# MicrobitBoardSensor.net
KiCad netlist of a schematic drawn in Altium Designer
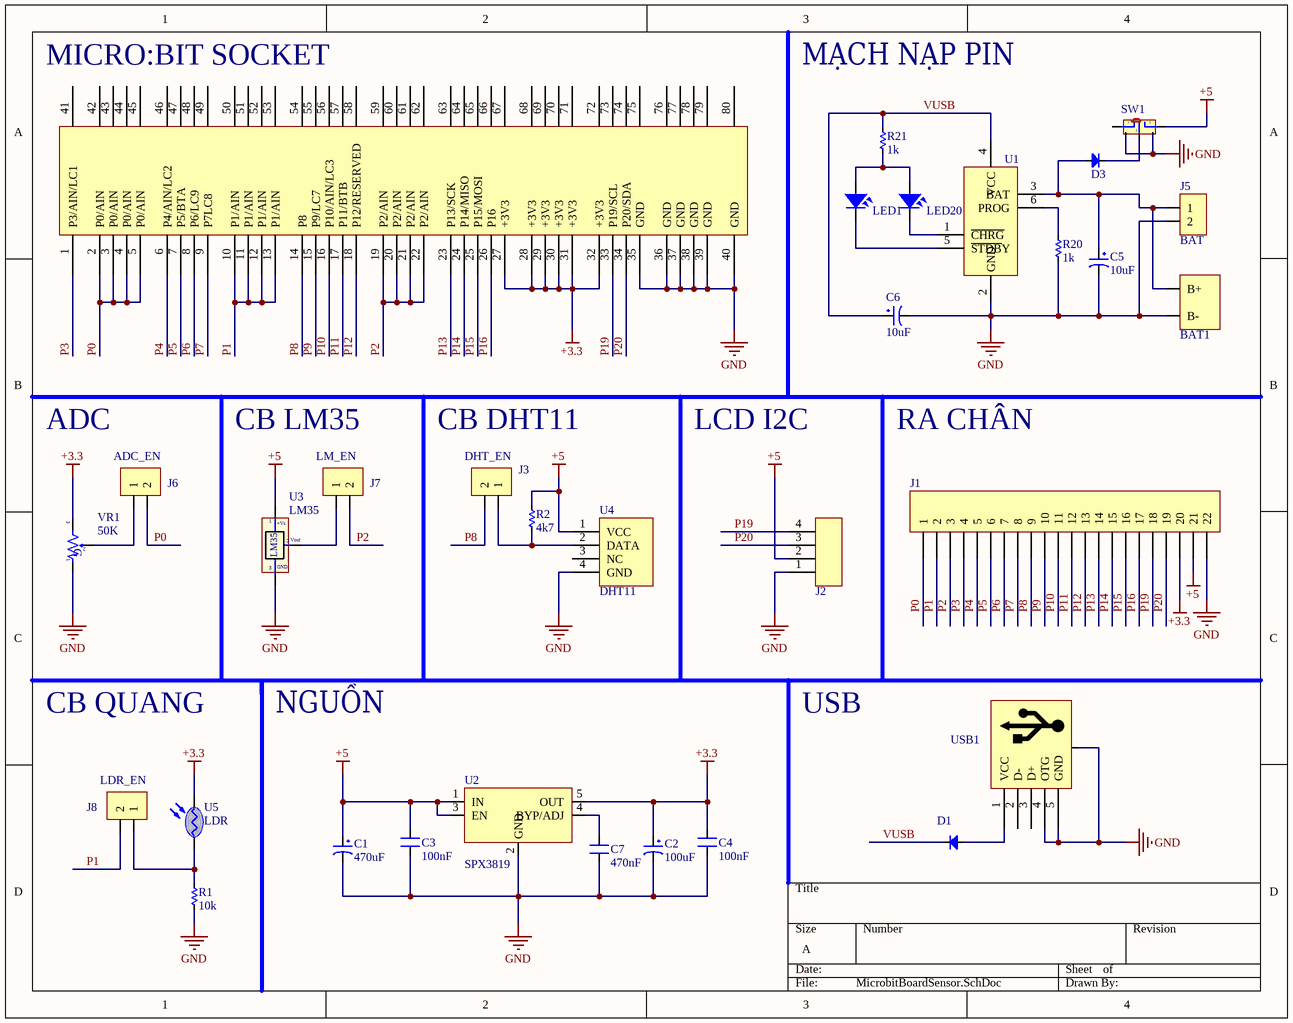
[diagram p0: MicrobitBoardSensor.SchDoc]

(export (version "E")
  (design (tool "Eeschema 10.0.6"))
  (components
    (comp (ref "BAT1")
      (value "BATERRY SOCKET")
      (footprint "BAT_SOCKET")
      (libsource (lib "User") (part "BAT_SOCKET"))
    )
    (comp (ref "BBC1")
      (value "BBC_SOCKET")
      (footprint "BBC_SK_DIP")
      (libsource (lib "microbit") (part "BBC_SOCKET"))
    )
    (comp (ref "C1")
      (value "470uF")
      (footprint "tu tantalum smd7343")
      (description "Dán")
      (libsource (lib "THU VIEN SCH_04042017_1") (part "Tu tantalum 470uF 10V SMD7343"))
    )
    (comp (ref "C2")
      (value "100uF")
      (footprint "tu tantalum smd3528")
      (description "Dán")
      (libsource (lib "THU VIEN SCH_04042017_1") (part "Tu tantalum 100uF 6.3V SMD3528"))
    )
    (comp (ref "C3") (value "100nF") (footprint "CN-SMD-0805") (libsource (lib "LIBRARY") (part "CN")))
    (comp (ref "C4") (value "100nF") (footprint "CN-SMD-0805") (libsource (lib "LIBRARY") (part "CN")))
    (comp (ref "C5")
      (value "10uF")
      (footprint "tu tantalum smd3528")
      (description "Dán")
      (libsource (lib "THU VIEN SCH_04042017_1") (part "Tu tantalum 10uF 16V SMD3528"))
    )
    (comp (ref "C6")
      (value "10uF")
      (footprint "tu tantalum smd3528")
      (description "Dán")
      (libsource (lib "") (part "Tu tantalum 10uF 16V SMD3528_1"))
    )
    (comp (ref "C7") (value "470nF") (footprint "CN-SMD-0805") (libsource (lib "LIBRARY") (part "CN")))
    (comp (ref "D1")
      (value "SS34")
      (footprint "DIO-SMD-123")
      (description "Default Diode")
      (fields (field (name "PUBLISHER") "Altium Limited"))
      (libsource (lib "LIBRARY") (part "Diode SMD"))
    )
    (comp (ref "D3")
      (value "SS34")
      (footprint "DIO-SMD-123")
      (description "Default Diode")
      (fields (field (name "PUBLISHER") "Altium Limited"))
      (libsource (lib "LIBRARY") (part "Diode SMD"))
    )
    (comp (ref "J1")
      (value "JP22")
      (footprint "JP22-D1T")
      (description "WR-PHD 2.54 mm Angled Socket Header")
      (fields
        (field (name "MANUFACTURER") "Würth Elektronik eiSos GmbH")
        (field (name "PARTNO") "613022143121")
        (field (name "CREATED BY") "Karrer Zheng")
      )
      (libsource (lib "LIBRARY") (part "JP22"))
    )
    (comp (ref "J2") (value "LCD IIC") (footprint "XH2.54-4P") (libsource (lib "User") (part "XH2.54-4P")))
    (comp (ref "J3")
      (value "DHT_EN")
      (footprint "JP2-CLOSED")
      (description "WR-PHD 2.54 mm Angled Socket Header")
      (fields
        (field (name "MANUFACTURER") "Würth Elektronik eiSos GmbH")
        (field (name "PARTNO") "613002143121")
        (field (name "CREATED BY") "Karrer Zheng")
      )
      (libsource (lib "") (part "JP2_1"))
    )
    (comp (ref "J5")
      (value "BAT")
      (footprint "JP2-D1T")
      (description "WR-PHD 2.54 mm Angled Socket Header")
      (fields
        (field (name "MANUFACTURER") "Würth Elektronik eiSos GmbH")
        (field (name "PARTNO") "613002143121")
        (field (name "CREATED BY") "Karrer Zheng")
      )
      (libsource (lib "") (part "JP2_1"))
    )
    (comp (ref "J6")
      (value "ADC_EN")
      (footprint "JP2-CLOSED")
      (description "WR-PHD 2.54 mm Angled Socket Header")
      (fields
        (field (name "MANUFACTURER") "Würth Elektronik eiSos GmbH")
        (field (name "PARTNO") "613002143121")
        (field (name "CREATED BY") "Karrer Zheng")
      )
      (libsource (lib "LIBRARY") (part "JP2"))
    )
    (comp (ref "J7")
      (value "LM_EN")
      (footprint "JP2-CLOSED")
      (description "WR-PHD 2.54 mm Angled Socket Header")
      (fields
        (field (name "MANUFACTURER") "Würth Elektronik eiSos GmbH")
        (field (name "PARTNO") "613002143121")
        (field (name "CREATED BY") "Karrer Zheng")
      )
      (libsource (lib "LIBRARY") (part "JP2"))
    )
    (comp (ref "J8")
      (value "LDR_EN")
      (footprint "JP2-CLOSED")
      (description "WR-PHD 2.54 mm Angled Socket Header")
      (fields
        (field (name "MANUFACTURER") "Würth Elektronik eiSos GmbH")
        (field (name "PARTNO") "613002143121")
        (field (name "CREATED BY") "Karrer Zheng")
      )
      (libsource (lib "") (part "JP2_1"))
    )
    (comp (ref "LED1") (value "F") (footprint "LED-0805-Blue") (libsource (lib "LIBRARY") (part "LED SMD")))
    (comp (ref "LED20") (value "C") (footprint "LED-0805-Blue") (libsource (lib "LIBRARY") (part "LED SMD")))
    (comp (ref "R1")
      (value "10k")
      (footprint "RES-SMD-0805")
      (description "Resistor")
      (fields
        (field (name "MANUFACTURER") "Generic Components")
        (field (name "PUBLISHER") "Altium Hobart Technology Centre")
      )
      (libsource (lib "LIBRARY") (part "Res-SMD"))
    )
    (comp (ref "R2")
      (value "4k7")
      (footprint "RES-SMD-0805")
      (description "Resistor")
      (fields
        (field (name "MANUFACTURER") "Generic Components")
        (field (name "PUBLISHER") "Altium Hobart Technology Centre")
      )
      (libsource (lib "LIBRARY") (part "Res-SMD"))
    )
    (comp (ref "R20")
      (value "1k")
      (footprint "RES-SMD-0805")
      (description "Resistor")
      (fields
        (field (name "MANUFACTURER") "Generic Components")
        (field (name "PUBLISHER") "Altium Hobart Technology Centre")
      )
      (libsource (lib "LIBRARY") (part "Res-SMD"))
    )
    (comp (ref "R21")
      (value "1k")
      (footprint "RES-SMD-0805")
      (description "Resistor")
      (fields
        (field (name "MANUFACTURER") "Generic Components")
        (field (name "PUBLISHER") "Altium Hobart Technology Centre")
      )
      (libsource (lib "LIBRARY") (part "Res-SMD"))
    )
    (comp (ref "SW1")
      (value "SW102A")
      (footprint "SW102")
      (description "Switch 102 on Broad")
      (libsource (lib "MH_THU VIEN CHUAN 12-03-2015") (part "SW102A"))
    )
    (comp (ref "U1") (value "TP4057") (footprint "SOT23-6") (libsource (lib "TP4057") (part "TP4057")))
    (comp (ref "U2") (value "SPX3819") (footprint "SOT23-5") (libsource (lib "TP4057") (part "SPX3819")))
    (comp (ref "U3")
      (value "LM35")
      (footprint "TO92-123")
      (description "Teminal")
      (libsource (lib "LIBRARY") (part "LM35"))
    )
    (comp (ref "U4") (value "DHT11") (footprint "DHT11") (libsource (lib "User") (part "DHT11")))
    (comp (ref "U5")
      (value "LDR")
      (footprint "CDS")
      (description "Quang Tro")
      (libsource (lib "LIBRARY") (part "LDR"))
    )
    (comp (ref "USB1") (value "PWR") (footprint "MicroUSB") (libsource (lib "User") (part "MicroUSB")))
    (comp (ref "VR1")
      (value "50K")
      (footprint "VR-S3")
      (description "Var Resistor")
      (libsource (lib "LIBRARY") (part "VR-S"))
    )
  )
  (nets
    (net (code "1") (name "+3.3") (class "Default")
      (node (ref "BBC1") (pin "27") (pinfunction "+3V3_27") (pintype "passive"))
      (node (ref "BBC1") (pin "28") (pinfunction "+3V3_28") (pintype "passive"))
      (node (ref "BBC1") (pin "29") (pinfunction "+3V3_29") (pintype "passive"))
      (node (ref "BBC1") (pin "30") (pinfunction "+3V3_30") (pintype "passive"))
      (node (ref "BBC1") (pin "31") (pinfunction "+3V3_31") (pintype "passive"))
      (node (ref "BBC1") (pin "32") (pinfunction "+3V3_32") (pintype "passive"))
      (node (ref "C2") (pin "1") (pinfunction "1_1") (pintype "passive"))
      (node (ref "C4") (pin "1") (pinfunction "1_1") (pintype "passive"))
      (node (ref "J1") (pin "20") (pinfunction "20_20") (pintype "passive"))
      (node (ref "U2") (pin "5") (pinfunction "OUT_5") (pintype "passive"))
      (node (ref "U5") (pin "2") (pinfunction "K_2") (pintype "passive"))
      (node (ref "VR1") (pin "3") (pinfunction "3_3") (pintype "passive"))
    )
    (net (code "2") (name "+5") (class "Default")
      (node (ref "C1") (pin "1") (pinfunction "1_1") (pintype "passive"))
      (node (ref "C3") (pin "1") (pinfunction "1_1") (pintype "passive"))
      (node (ref "J1") (pin "21") (pinfunction "21_21") (pintype "passive"))
      (node (ref "J2") (pin "2") (pinfunction "2_2") (pintype "passive"))
      (node (ref "R2") (pin "1") (pinfunction "1_1") (pintype "passive"))
      (node (ref "SW1") (pin "3") (pinfunction "3_3") (pintype "passive"))
      (node (ref "U2") (pin "1") (pinfunction "IN_1") (pintype "passive"))
      (node (ref "U2") (pin "3") (pinfunction "EN_3") (pintype "passive"))
      (node (ref "U3") (pin "1") (pinfunction "+Vs_1") (pintype "passive"))
      (node (ref "U4") (pin "1") (pinfunction "VCC_1") (pintype "passive"))
    )
    (net (code "3") (name "/P0") (class "Default")
      (node (ref "BBC1") (pin "2") (pinfunction "P0/AIN_2") (pintype "passive"))
      (node (ref "BBC1") (pin "3") (pinfunction "P0/AIN_3") (pintype "passive"))
      (node (ref "BBC1") (pin "4") (pinfunction "P0/AIN_4") (pintype "passive"))
      (node (ref "BBC1") (pin "5") (pinfunction "P0/AIN_5") (pintype "passive"))
      (node (ref "J1") (pin "1") (pinfunction "1_1") (pintype "passive"))
      (node (ref "J6") (pin "2") (pinfunction "2_2") (pintype "passive"))
    )
    (net (code "4") (name "/P1") (class "Default")
      (node (ref "BBC1") (pin "10") (pinfunction "P1/AIN_10") (pintype "passive"))
      (node (ref "BBC1") (pin "11") (pinfunction "P1/AIN_11") (pintype "passive"))
      (node (ref "BBC1") (pin "12") (pinfunction "P1/AIN_12") (pintype "passive"))
      (node (ref "BBC1") (pin "13") (pinfunction "P1/AIN_13") (pintype "passive"))
      (node (ref "J1") (pin "2") (pinfunction "2_2") (pintype "passive"))
      (node (ref "J8") (pin "2") (pinfunction "2_2") (pintype "passive"))
    )
    (net (code "5") (name "/P2") (class "Default")
      (node (ref "BBC1") (pin "19") (pinfunction "P2/AIN_19") (pintype "passive"))
      (node (ref "BBC1") (pin "20") (pinfunction "P2/AIN_20") (pintype "passive"))
      (node (ref "BBC1") (pin "21") (pinfunction "P2/AIN_21") (pintype "passive"))
      (node (ref "BBC1") (pin "22") (pinfunction "P2/AIN_22") (pintype "passive"))
      (node (ref "J1") (pin "3") (pinfunction "3_3") (pintype "passive"))
      (node (ref "J7") (pin "2") (pinfunction "2_2") (pintype "passive"))
    )
    (net (code "6") (name "/P3") (class "Default")
      (node (ref "BBC1") (pin "1") (pinfunction "P3/AIN/LC1_1") (pintype "passive"))
      (node (ref "J1") (pin "4") (pinfunction "4_4") (pintype "passive"))
    )
    (net (code "7") (name "/P4") (class "Default")
      (node (ref "BBC1") (pin "6") (pinfunction "P4/AIN/LC2_6") (pintype "passive"))
      (node (ref "J1") (pin "5") (pinfunction "5_5") (pintype "passive"))
    )
    (net (code "8") (name "/P5") (class "Default")
      (node (ref "BBC1") (pin "7") (pinfunction "P5/BTA_7") (pintype "passive"))
      (node (ref "J1") (pin "6") (pinfunction "6_6") (pintype "passive"))
    )
    (net (code "9") (name "/P6") (class "Default")
      (node (ref "BBC1") (pin "8") (pinfunction "P6/LC9_8") (pintype "passive"))
      (node (ref "J1") (pin "7") (pinfunction "7_7") (pintype "passive"))
    )
    (net (code "10") (name "/P7") (class "Default")
      (node (ref "BBC1") (pin "9") (pinfunction "P7LC8_9") (pintype "passive"))
      (node (ref "J1") (pin "8") (pinfunction "8_8") (pintype "passive"))
    )
    (net (code "11") (name "/P8") (class "Default")
      (node (ref "BBC1") (pin "14") (pinfunction "P8_14") (pintype "passive"))
      (node (ref "J1") (pin "9") (pinfunction "9_9") (pintype "passive"))
      (node (ref "J3") (pin "2") (pinfunction "2_2") (pintype "passive"))
    )
    (net (code "12") (name "/P9") (class "Default")
      (node (ref "BBC1") (pin "15") (pinfunction "P9/LC7_15") (pintype "passive"))
      (node (ref "J1") (pin "10") (pinfunction "10_10") (pintype "passive"))
    )
    (net (code "13") (name "/P10") (class "Default")
      (node (ref "BBC1") (pin "16") (pinfunction "P10/AIN/LC3_16") (pintype "passive"))
      (node (ref "J1") (pin "11") (pinfunction "11_11") (pintype "passive"))
    )
    (net (code "14") (name "/P11") (class "Default")
      (node (ref "BBC1") (pin "17") (pinfunction "P11/BTB_17") (pintype "passive"))
      (node (ref "J1") (pin "12") (pinfunction "12_12") (pintype "passive"))
    )
    (net (code "15") (name "/P12") (class "Default")
      (node (ref "BBC1") (pin "18") (pinfunction "P12/RESERVED_18") (pintype "passive"))
      (node (ref "J1") (pin "13") (pinfunction "13_13") (pintype "passive"))
    )
    (net (code "16") (name "/P13") (class "Default")
      (node (ref "BBC1") (pin "23") (pinfunction "P13/SCK_23") (pintype "passive"))
      (node (ref "J1") (pin "14") (pinfunction "14_14") (pintype "passive"))
    )
    (net (code "17") (name "/P14") (class "Default")
      (node (ref "BBC1") (pin "24") (pinfunction "P14/MISO_24") (pintype "passive"))
      (node (ref "J1") (pin "15") (pinfunction "15_15") (pintype "passive"))
    )
    (net (code "18") (name "/P15") (class "Default")
      (node (ref "BBC1") (pin "25") (pinfunction "P15/MOSI_25") (pintype "passive"))
      (node (ref "J1") (pin "16") (pinfunction "16_16") (pintype "passive"))
    )
    (net (code "19") (name "/P16") (class "Default")
      (node (ref "BBC1") (pin "26") (pinfunction "P16_26") (pintype "passive"))
      (node (ref "J1") (pin "17") (pinfunction "17_17") (pintype "passive"))
    )
    (net (code "20") (name "/P19") (class "Default")
      (node (ref "BBC1") (pin "33") (pinfunction "P19/SCL_33") (pintype "passive"))
      (node (ref "J1") (pin "18") (pinfunction "18_18") (pintype "passive"))
      (node (ref "J2") (pin "4") (pinfunction "4_4") (pintype "passive"))
    )
    (net (code "21") (name "/P20") (class "Default")
      (node (ref "BBC1") (pin "34") (pinfunction "P20/SDA_34") (pintype "passive"))
      (node (ref "J1") (pin "19") (pinfunction "19_19") (pintype "passive"))
      (node (ref "J2") (pin "3") (pinfunction "3_3") (pintype "passive"))
    )
    (net (code "22") (name "/VUSB") (class "Default")
      (node (ref "C6") (pin "1") (pinfunction "1_1") (pintype "passive"))
      (node (ref "D1") (pin "2") (pinfunction "K_2") (pintype "passive"))
      (node (ref "R21") (pin "2") (pinfunction "2_2") (pintype "passive"))
      (node (ref "U1") (pin "4") (pinfunction "VCC_4") (pintype "passive"))
    )
    (net (code "23") (name "GND") (class "Default")
      (node (ref "BAT1") (pin "2") (pinfunction "B-_2") (pintype "passive"))
      (node (ref "BBC1") (pin "35") (pinfunction "GND_35") (pintype "passive"))
      (node (ref "BBC1") (pin "36") (pinfunction "GND_36") (pintype "passive"))
      (node (ref "BBC1") (pin "37") (pinfunction "GND_37") (pintype "passive"))
      (node (ref "BBC1") (pin "38") (pinfunction "GND_38") (pintype "passive"))
      (node (ref "BBC1") (pin "39") (pinfunction "GND_39") (pintype "passive"))
      (node (ref "BBC1") (pin "40") (pinfunction "GND_40") (pintype "passive"))
      (node (ref "C1") (pin "2") (pinfunction "2_2") (pintype "passive"))
      (node (ref "C2") (pin "2") (pinfunction "2_2") (pintype "passive"))
      (node (ref "C3") (pin "2") (pinfunction "2_2") (pintype "passive"))
      (node (ref "C4") (pin "2") (pinfunction "2_2") (pintype "passive"))
      (node (ref "C5") (pin "2") (pinfunction "2_2") (pintype "passive"))
      (node (ref "C6") (pin "2") (pinfunction "2_2") (pintype "passive"))
      (node (ref "C7") (pin "2") (pinfunction "2_2") (pintype "passive"))
      (node (ref "J1") (pin "22") (pinfunction "22_22") (pintype "passive"))
      (node (ref "J2") (pin "1") (pinfunction "1_1") (pintype "passive"))
      (node (ref "J5") (pin "2") (pinfunction "2_2") (pintype "passive"))
      (node (ref "R1") (pin "2") (pinfunction "2_2") (pintype "passive"))
      (node (ref "R20") (pin "1") (pinfunction "1_1") (pintype "passive"))
      (node (ref "SW1") (pin "4") (pinfunction "4_4") (pintype "passive"))
      (node (ref "SW1") (pin "5") (pinfunction "5_5") (pintype "passive"))
      (node (ref "U1") (pin "2") (pinfunction "GND_2") (pintype "passive"))
      (node (ref "U2") (pin "2") (pinfunction "GND_2") (pintype "passive"))
      (node (ref "U3") (pin "3") (pinfunction "-_3") (pintype "passive"))
      (node (ref "U4") (pin "4") (pinfunction "GND_4") (pintype "passive"))
      (node (ref "USB1") (pin "0") (pinfunction "GND_0") (pintype "passive"))
      (node (ref "USB1") (pin "4") (pinfunction "OTG_4") (pintype "passive"))
      (node (ref "USB1") (pin "5") (pinfunction "GND_5") (pintype "passive"))
      (node (ref "VR1") (pin "1") (pinfunction "1_1") (pintype "passive"))
    )
    (net (code "24") (name "Net-(BAT1-B+)") (class "Default")
      (node (ref "BAT1") (pin "1") (pinfunction "B+_1") (pintype "passive"))
      (node (ref "C5") (pin "1") (pinfunction "1_1") (pintype "passive"))
      (node (ref "D3") (pin "1") (pinfunction "A_1") (pintype "passive"))
      (node (ref "J5") (pin "1") (pinfunction "1_1") (pintype "passive"))
      (node (ref "U1") (pin "3") (pinfunction "BAT_3") (pintype "passive"))
    )
    (net (code "25") (name "Net-(D1-A)") (class "Default")
      (node (ref "D1") (pin "1") (pinfunction "A_1") (pintype "passive"))
      (node (ref "USB1") (pin "1") (pinfunction "VCC_1") (pintype "passive"))
    )
    (net (code "26") (name "Net-(D3-K)") (class "Default")
      (node (ref "D3") (pin "2") (pinfunction "K_2") (pintype "passive"))
      (node (ref "SW1") (pin "2") (pinfunction "2_2") (pintype "passive"))
    )
    (net (code "27") (name "Net-(J6-Pad1)") (class "Default")
      (node (ref "J6") (pin "1") (pinfunction "1_1") (pintype "passive"))
      (node (ref "VR1") (pin "2") (pinfunction "2_2") (pintype "passive"))
    )
    (net (code "28") (name "Net-(LED1-Pad1)") (class "Default")
      (node (ref "LED1") (pin "1") (pinfunction "1_1") (pintype "passive"))
      (node (ref "LED20") (pin "1") (pinfunction "1_1") (pintype "passive"))
      (node (ref "R21") (pin "1") (pinfunction "1_1") (pintype "passive"))
    )
    (net (code "29") (name "Net-(U1-PROG)") (class "Default")
      (node (ref "R20") (pin "2") (pinfunction "2_2") (pintype "passive"))
      (node (ref "U1") (pin "6") (pinfunction "PROG_6") (pintype "passive"))
    )
    (net (code "30") (name "Net-(U1-~{CHRG})") (class "Default")
      (node (ref "LED20") (pin "2") (pinfunction "2_2") (pintype "passive"))
      (node (ref "U1") (pin "1") (pinfunction "~{CHRG}_1") (pintype "passive"))
    )
    (net (code "31") (name "Net-(U1-~{STDB}Y)") (class "Default")
      (node (ref "LED1") (pin "2") (pinfunction "2_2") (pintype "passive"))
      (node (ref "U1") (pin "5") (pinfunction "~{STDB}Y_5") (pintype "passive"))
    )
    (net (code "32") (name "Net-(U2-BYP{slash}ADJ)") (class "Default")
      (node (ref "C7") (pin "1") (pinfunction "1_1") (pintype "passive"))
      (node (ref "U2") (pin "4") (pinfunction "BYP/ADJ_4") (pintype "passive"))
    )
    (net (code "33") (name "Net-(U3-Vout)") (class "Default")
      (node (ref "J7") (pin "1") (pinfunction "1_1") (pintype "passive"))
      (node (ref "U3") (pin "2") (pinfunction "Vout_2") (pintype "passive"))
    )
    (net (code "34") (name "Net-(U4-DATA)") (class "Default")
      (node (ref "J3") (pin "1") (pinfunction "1_1") (pintype "passive"))
      (node (ref "R2") (pin "2") (pinfunction "2_2") (pintype "passive"))
      (node (ref "U4") (pin "2") (pinfunction "DATA_2") (pintype "passive"))
    )
    (net (code "35") (name "Net-(U5-A)") (class "Default")
      (node (ref "J8") (pin "1") (pinfunction "1_1") (pintype "passive"))
      (node (ref "R1") (pin "1") (pinfunction "1_1") (pintype "passive"))
      (node (ref "U5") (pin "1") (pinfunction "A_1") (pintype "passive"))
    )
    (net (code "36") (name "unconnected-(BBC1-+3V3-Pad67)") (class "Default")
      (node (ref "BBC1") (pin "67") (pinfunction "+3V3_67") (pintype "passive"))
    )
    (net (code "37") (name "unconnected-(BBC1-+3V3-Pad68)") (class "Default")
      (node (ref "BBC1") (pin "68") (pinfunction "+3V3_68") (pintype "passive"))
    )
    (net (code "38") (name "unconnected-(BBC1-+3V3-Pad69)") (class "Default")
      (node (ref "BBC1") (pin "69") (pinfunction "+3V3_69") (pintype "passive"))
    )
    (net (code "39") (name "unconnected-(BBC1-+3V3-Pad70)") (class "Default")
      (node (ref "BBC1") (pin "70") (pinfunction "+3V3_70") (pintype "passive"))
    )
    (net (code "40") (name "unconnected-(BBC1-+3V3-Pad71)") (class "Default")
      (node (ref "BBC1") (pin "71") (pinfunction "+3V3_71") (pintype "passive"))
    )
    (net (code "41") (name "unconnected-(BBC1-+3V3-Pad72)") (class "Default")
      (node (ref "BBC1") (pin "72") (pinfunction "+3V3_72") (pintype "passive"))
    )
    (net (code "42") (name "unconnected-(BBC1-GND-Pad75)") (class "Default")
      (node (ref "BBC1") (pin "75") (pinfunction "GND_75") (pintype "passive"))
    )
    (net (code "43") (name "unconnected-(BBC1-GND-Pad76)") (class "Default")
      (node (ref "BBC1") (pin "76") (pinfunction "GND_76") (pintype "passive"))
    )
    (net (code "44") (name "unconnected-(BBC1-GND-Pad77)") (class "Default")
      (node (ref "BBC1") (pin "77") (pinfunction "GND_77") (pintype "passive"))
    )
    (net (code "45") (name "unconnected-(BBC1-GND-Pad78)") (class "Default")
      (node (ref "BBC1") (pin "78") (pinfunction "GND_78") (pintype "passive"))
    )
    (net (code "46") (name "unconnected-(BBC1-GND-Pad79)") (class "Default")
      (node (ref "BBC1") (pin "79") (pinfunction "GND_79") (pintype "passive"))
    )
    (net (code "47") (name "unconnected-(BBC1-GND-Pad80)") (class "Default")
      (node (ref "BBC1") (pin "80") (pinfunction "GND_80") (pintype "passive"))
    )
    (net (code "48") (name "unconnected-(BBC1-P0-Pad42)") (class "Default")
      (node (ref "BBC1") (pin "42") (pinfunction "P0_42") (pintype "passive"))
    )
    (net (code "49") (name "unconnected-(BBC1-P0-Pad43)") (class "Default")
      (node (ref "BBC1") (pin "43") (pinfunction "P0_43") (pintype "passive"))
    )
    (net (code "50") (name "unconnected-(BBC1-P0-Pad44)") (class "Default")
      (node (ref "BBC1") (pin "44") (pinfunction "P0_44") (pintype "passive"))
    )
    (net (code "51") (name "unconnected-(BBC1-P0-Pad45)") (class "Default")
      (node (ref "BBC1") (pin "45") (pinfunction "P0_45") (pintype "passive"))
    )
    (net (code "52") (name "unconnected-(BBC1-P1-Pad50)") (class "Default")
      (node (ref "BBC1") (pin "50") (pinfunction "P1_50") (pintype "passive"))
    )
    (net (code "53") (name "unconnected-(BBC1-P1-Pad51)") (class "Default")
      (node (ref "BBC1") (pin "51") (pinfunction "P1_51") (pintype "passive"))
    )
    (net (code "54") (name "unconnected-(BBC1-P1-Pad52)") (class "Default")
      (node (ref "BBC1") (pin "52") (pinfunction "P1_52") (pintype "passive"))
    )
    (net (code "55") (name "unconnected-(BBC1-P1-Pad53)") (class "Default")
      (node (ref "BBC1") (pin "53") (pinfunction "P1_53") (pintype "passive"))
    )
    (net (code "56") (name "unconnected-(BBC1-P2-Pad59)") (class "Default")
      (node (ref "BBC1") (pin "59") (pinfunction "P2_59") (pintype "passive"))
    )
    (net (code "57") (name "unconnected-(BBC1-P2-Pad60)") (class "Default")
      (node (ref "BBC1") (pin "60") (pinfunction "P2_60") (pintype "passive"))
    )
    (net (code "58") (name "unconnected-(BBC1-P2-Pad61)") (class "Default")
      (node (ref "BBC1") (pin "61") (pinfunction "P2_61") (pintype "passive"))
    )
    (net (code "59") (name "unconnected-(BBC1-P2-Pad62)") (class "Default")
      (node (ref "BBC1") (pin "62") (pinfunction "P2_62") (pintype "passive"))
    )
    (net (code "60") (name "unconnected-(BBC1-P3-Pad41)") (class "Default")
      (node (ref "BBC1") (pin "41") (pinfunction "P3_41") (pintype "passive"))
    )
    (net (code "61") (name "unconnected-(BBC1-P4-Pad46)") (class "Default")
      (node (ref "BBC1") (pin "46") (pinfunction "P4_46") (pintype "passive"))
    )
    (net (code "62") (name "unconnected-(BBC1-P5-Pad47)") (class "Default")
      (node (ref "BBC1") (pin "47") (pinfunction "P5_47") (pintype "passive"))
    )
    (net (code "63") (name "unconnected-(BBC1-P6-Pad48)") (class "Default")
      (node (ref "BBC1") (pin "48") (pinfunction "P6_48") (pintype "passive"))
    )
    (net (code "64") (name "unconnected-(BBC1-P7-Pad49)") (class "Default")
      (node (ref "BBC1") (pin "49") (pinfunction "P7_49") (pintype "passive"))
    )
    (net (code "65") (name "unconnected-(BBC1-P8-Pad54)") (class "Default")
      (node (ref "BBC1") (pin "54") (pinfunction "P8_54") (pintype "passive"))
    )
    (net (code "66") (name "unconnected-(BBC1-P9-Pad55)") (class "Default")
      (node (ref "BBC1") (pin "55") (pinfunction "P9_55") (pintype "passive"))
    )
    (net (code "67") (name "unconnected-(BBC1-P10-Pad56)") (class "Default")
      (node (ref "BBC1") (pin "56") (pinfunction "P10_56") (pintype "passive"))
    )
    (net (code "68") (name "unconnected-(BBC1-P11-Pad57)") (class "Default")
      (node (ref "BBC1") (pin "57") (pinfunction "P11_57") (pintype "passive"))
    )
    (net (code "69") (name "unconnected-(BBC1-P12-Pad58)") (class "Default")
      (node (ref "BBC1") (pin "58") (pinfunction "P12_58") (pintype "passive"))
    )
    (net (code "70") (name "unconnected-(BBC1-P13-Pad63)") (class "Default")
      (node (ref "BBC1") (pin "63") (pinfunction "P13_63") (pintype "passive"))
    )
    (net (code "71") (name "unconnected-(BBC1-P14-Pad64)") (class "Default")
      (node (ref "BBC1") (pin "64") (pinfunction "P14_64") (pintype "passive"))
    )
    (net (code "72") (name "unconnected-(BBC1-P15-Pad65)") (class "Default")
      (node (ref "BBC1") (pin "65") (pinfunction "P15_65") (pintype "passive"))
    )
    (net (code "73") (name "unconnected-(BBC1-P16-Pad66)") (class "Default")
      (node (ref "BBC1") (pin "66") (pinfunction "P16_66") (pintype "passive"))
    )
    (net (code "74") (name "unconnected-(BBC1-P19-Pad73)") (class "Default")
      (node (ref "BBC1") (pin "73") (pinfunction "P19_73") (pintype "passive"))
    )
    (net (code "75") (name "unconnected-(BBC1-P20-Pad74)") (class "Default")
      (node (ref "BBC1") (pin "74") (pinfunction "P20_74") (pintype "passive"))
    )
    (net (code "76") (name "unconnected-(SW1-Pad1)") (class "Default")
      (node (ref "SW1") (pin "1") (pinfunction "1_1") (pintype "passive"))
    )
    (net (code "77") (name "unconnected-(U4-NC-Pad3)") (class "Default")
      (node (ref "U4") (pin "3") (pinfunction "NC_3") (pintype "passive"))
    )
    (net (code "78") (name "unconnected-(USB1-D+-Pad3)") (class "Default")
      (node (ref "USB1") (pin "3") (pinfunction "D+_3") (pintype "passive"))
    )
    (net (code "79") (name "unconnected-(USB1-D--Pad2)") (class "Default")
      (node (ref "USB1") (pin "2") (pinfunction "D-_2") (pintype "passive"))
    )
  )
)
